# TLC5955.net
KiCad netlist of a schematic drawn in EAGLE
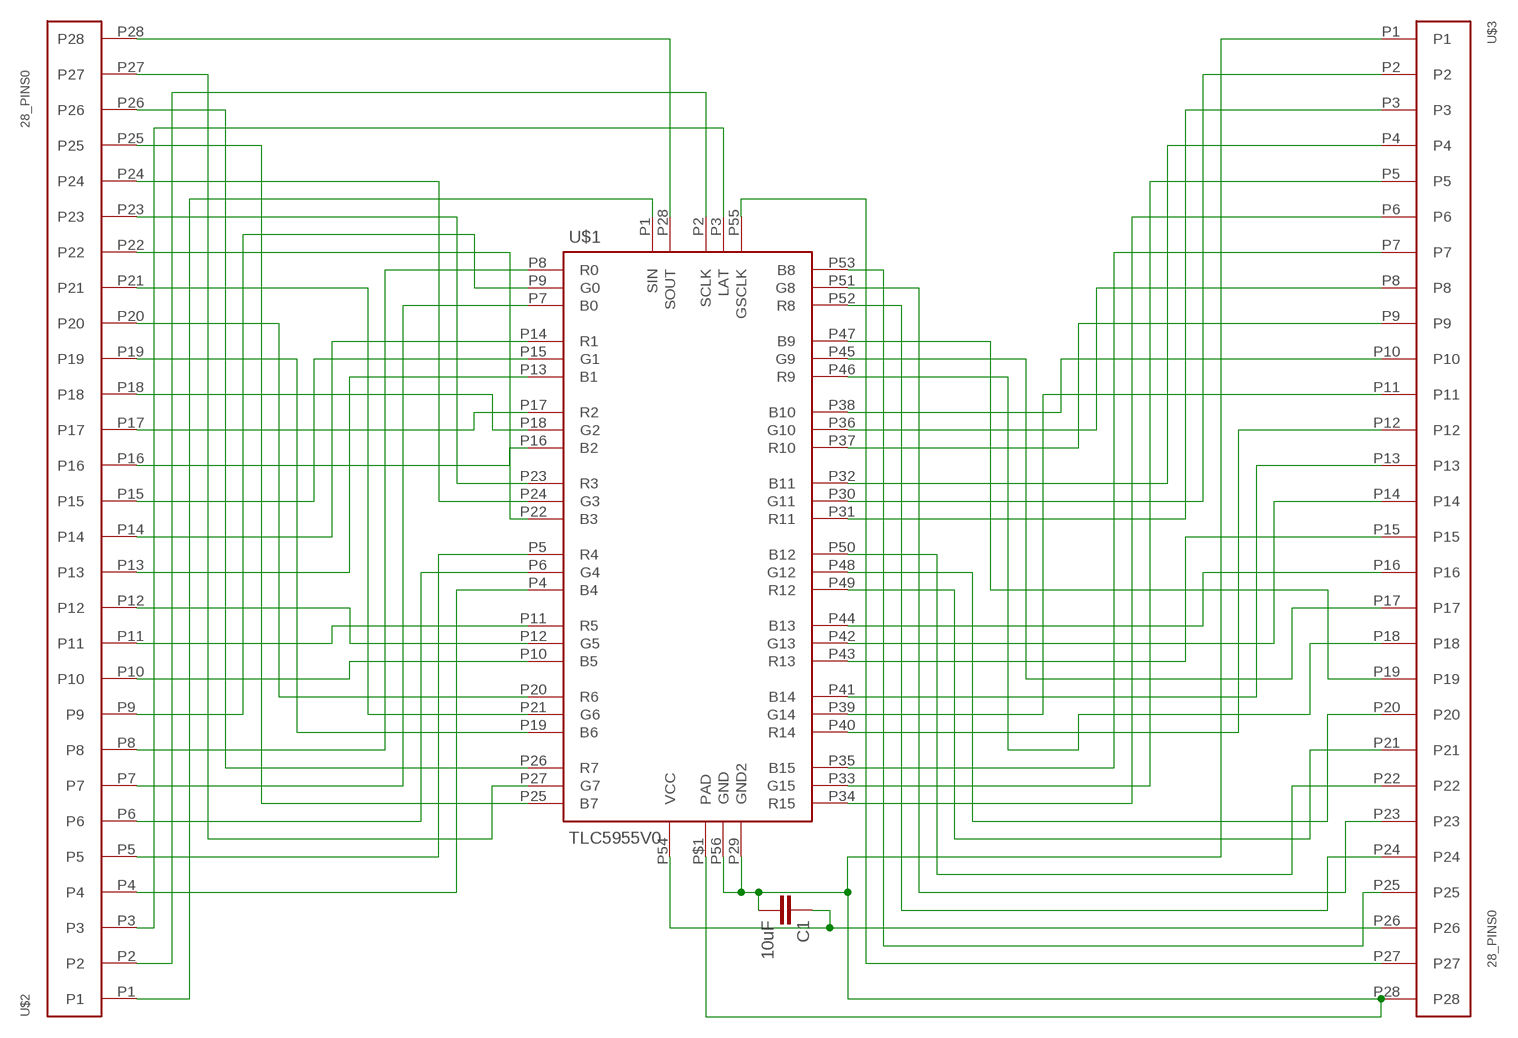
[diagram p0: schematic, sheet 1]

(export (version "E")
  (design (tool "Eeschema 10.0.6"))
  (components
    (comp (ref "C1")
      (value "10uF")
      (footprint "eagle-import:0603-CAP")
      (libsource (lib "eagle-import") (part "10UF-6.3V-20%(0603)"))
    )
    (comp (ref "U$1")
      (value "TLC5955V0")
      (footprint "eagle-import:56-HTSSOP")
      (libsource (lib "eagle-import") (part "TLC5955V0"))
    )
    (comp (ref "U$2")
      (value "28_PINS0")
      (footprint "eagle-import:28PIN_HOLES")
      (libsource (lib "eagle-import") (part "28_PINS0"))
    )
    (comp (ref "U$3")
      (value "28_PINS0")
      (footprint "eagle-import:28PIN_HOLES")
      (libsource (lib "eagle-import") (part "28_PINS0"))
    )
  )
  (nets
    (net (code "1") (name "Net-(U$1-B0)") (class "Default")
      (node (ref "U$1") (pin "P7") (pinfunction "B0_P7") (pintype "bidirectional"))
      (node (ref "U$2") (pin "P7") (pinfunction "P7_P7") (pintype "bidirectional"))
    )
    (net (code "2") (name "Net-(U$1-B1)") (class "Default")
      (node (ref "U$1") (pin "P13") (pinfunction "B1_P13") (pintype "bidirectional"))
      (node (ref "U$2") (pin "P13") (pinfunction "P13_P13") (pintype "bidirectional"))
    )
    (net (code "3") (name "Net-(U$1-B2)") (class "Default")
      (node (ref "U$1") (pin "P16") (pinfunction "B2_P16") (pintype "bidirectional"))
      (node (ref "U$2") (pin "P16") (pinfunction "P16_P16") (pintype "bidirectional"))
    )
    (net (code "4") (name "Net-(U$1-B3)") (class "Default")
      (node (ref "U$1") (pin "P22") (pinfunction "B3_P22") (pintype "bidirectional"))
      (node (ref "U$2") (pin "P22") (pinfunction "P22_P22") (pintype "bidirectional"))
    )
    (net (code "5") (name "Net-(U$1-B4)") (class "Default")
      (node (ref "U$1") (pin "P4") (pinfunction "B4_P4") (pintype "bidirectional"))
      (node (ref "U$2") (pin "P4") (pinfunction "P4_P4") (pintype "bidirectional"))
    )
    (net (code "6") (name "Net-(U$1-B5)") (class "Default")
      (node (ref "U$1") (pin "P10") (pinfunction "B5_P10") (pintype "bidirectional"))
      (node (ref "U$2") (pin "P10") (pinfunction "P10_P10") (pintype "bidirectional"))
    )
    (net (code "7") (name "Net-(U$1-B6)") (class "Default")
      (node (ref "U$1") (pin "P19") (pinfunction "B6_P19") (pintype "bidirectional"))
      (node (ref "U$2") (pin "P19") (pinfunction "P19_P19") (pintype "bidirectional"))
    )
    (net (code "8") (name "Net-(U$1-B7)") (class "Default")
      (node (ref "U$1") (pin "P25") (pinfunction "B7_P25") (pintype "bidirectional"))
      (node (ref "U$2") (pin "P25") (pinfunction "P25_P25") (pintype "bidirectional"))
    )
    (net (code "9") (name "Net-(U$1-B8)") (class "Default")
      (node (ref "U$1") (pin "P53") (pinfunction "B8_P53") (pintype "bidirectional"))
      (node (ref "U$3") (pin "P25") (pinfunction "P25_P25") (pintype "bidirectional"))
    )
    (net (code "10") (name "Net-(U$1-B9)") (class "Default")
      (node (ref "U$1") (pin "P47") (pinfunction "B9_P47") (pintype "bidirectional"))
      (node (ref "U$3") (pin "P19") (pinfunction "P19_P19") (pintype "bidirectional"))
    )
    (net (code "11") (name "Net-(U$1-B10)") (class "Default")
      (node (ref "U$1") (pin "P38") (pinfunction "B10_P38") (pintype "bidirectional"))
      (node (ref "U$3") (pin "P10") (pinfunction "P10_P10") (pintype "bidirectional"))
    )
    (net (code "12") (name "Net-(U$1-B11)") (class "Default")
      (node (ref "U$1") (pin "P32") (pinfunction "B11_P32") (pintype "bidirectional"))
      (node (ref "U$3") (pin "P4") (pinfunction "P4_P4") (pintype "bidirectional"))
    )
    (net (code "13") (name "Net-(U$1-B12)") (class "Default")
      (node (ref "U$1") (pin "P50") (pinfunction "B12_P50") (pintype "bidirectional"))
      (node (ref "U$3") (pin "P22") (pinfunction "P22_P22") (pintype "bidirectional"))
    )
    (net (code "14") (name "Net-(U$1-B13)") (class "Default")
      (node (ref "U$1") (pin "P44") (pinfunction "B13_P44") (pintype "bidirectional"))
      (node (ref "U$3") (pin "P16") (pinfunction "P16_P16") (pintype "bidirectional"))
    )
    (net (code "15") (name "Net-(U$1-B14)") (class "Default")
      (node (ref "U$1") (pin "P41") (pinfunction "B14_P41") (pintype "bidirectional"))
      (node (ref "U$3") (pin "P13") (pinfunction "P13_P13") (pintype "bidirectional"))
    )
    (net (code "16") (name "Net-(U$1-B15)") (class "Default")
      (node (ref "U$1") (pin "P35") (pinfunction "B15_P35") (pintype "bidirectional"))
      (node (ref "U$3") (pin "P7") (pinfunction "P7_P7") (pintype "bidirectional"))
    )
    (net (code "17") (name "Net-(U$1-G0)") (class "Default")
      (node (ref "U$1") (pin "P9") (pinfunction "G0_P9") (pintype "bidirectional"))
      (node (ref "U$2") (pin "P9") (pinfunction "P9_P9") (pintype "bidirectional"))
    )
    (net (code "18") (name "Net-(U$1-G1)") (class "Default")
      (node (ref "U$1") (pin "P15") (pinfunction "G1_P15") (pintype "bidirectional"))
      (node (ref "U$2") (pin "P15") (pinfunction "P15_P15") (pintype "bidirectional"))
    )
    (net (code "19") (name "Net-(U$1-G2)") (class "Default")
      (node (ref "U$1") (pin "P18") (pinfunction "G2_P18") (pintype "bidirectional"))
      (node (ref "U$2") (pin "P18") (pinfunction "P18_P18") (pintype "bidirectional"))
    )
    (net (code "20") (name "Net-(U$1-G3)") (class "Default")
      (node (ref "U$1") (pin "P24") (pinfunction "G3_P24") (pintype "bidirectional"))
      (node (ref "U$2") (pin "P24") (pinfunction "P24_P24") (pintype "bidirectional"))
    )
    (net (code "21") (name "Net-(U$1-G4)") (class "Default")
      (node (ref "U$1") (pin "P6") (pinfunction "G4_P6") (pintype "bidirectional"))
      (node (ref "U$2") (pin "P6") (pinfunction "P6_P6") (pintype "bidirectional"))
    )
    (net (code "22") (name "Net-(U$1-G5)") (class "Default")
      (node (ref "U$1") (pin "P12") (pinfunction "G5_P12") (pintype "bidirectional"))
      (node (ref "U$2") (pin "P12") (pinfunction "P12_P12") (pintype "bidirectional"))
    )
    (net (code "23") (name "Net-(U$1-G6)") (class "Default")
      (node (ref "U$1") (pin "P21") (pinfunction "G6_P21") (pintype "bidirectional"))
      (node (ref "U$2") (pin "P21") (pinfunction "P21_P21") (pintype "bidirectional"))
    )
    (net (code "24") (name "Net-(U$1-G7)") (class "Default")
      (node (ref "U$1") (pin "P27") (pinfunction "G7_P27") (pintype "bidirectional"))
      (node (ref "U$2") (pin "P27") (pinfunction "P27_P27") (pintype "bidirectional"))
    )
    (net (code "25") (name "Net-(U$1-G8)") (class "Default")
      (node (ref "U$1") (pin "P51") (pinfunction "G8_P51") (pintype "bidirectional"))
      (node (ref "U$3") (pin "P23") (pinfunction "P23_P23") (pintype "bidirectional"))
    )
    (net (code "26") (name "Net-(U$1-G9)") (class "Default")
      (node (ref "U$1") (pin "P45") (pinfunction "G9_P45") (pintype "bidirectional"))
      (node (ref "U$3") (pin "P17") (pinfunction "P17_P17") (pintype "bidirectional"))
    )
    (net (code "27") (name "Net-(U$1-G10)") (class "Default")
      (node (ref "U$1") (pin "P36") (pinfunction "G10_P36") (pintype "bidirectional"))
      (node (ref "U$3") (pin "P8") (pinfunction "P8_P8") (pintype "bidirectional"))
    )
    (net (code "28") (name "Net-(U$1-G11)") (class "Default")
      (node (ref "U$1") (pin "P30") (pinfunction "G11_P30") (pintype "bidirectional"))
      (node (ref "U$3") (pin "P2") (pinfunction "P2_P2") (pintype "bidirectional"))
    )
    (net (code "29") (name "Net-(U$1-G12)") (class "Default")
      (node (ref "U$1") (pin "P48") (pinfunction "G12_P48") (pintype "bidirectional"))
      (node (ref "U$3") (pin "P20") (pinfunction "P20_P20") (pintype "bidirectional"))
    )
    (net (code "30") (name "Net-(U$1-G13)") (class "Default")
      (node (ref "U$1") (pin "P42") (pinfunction "G13_P42") (pintype "bidirectional"))
      (node (ref "U$3") (pin "P14") (pinfunction "P14_P14") (pintype "bidirectional"))
    )
    (net (code "31") (name "Net-(U$1-G14)") (class "Default")
      (node (ref "U$1") (pin "P39") (pinfunction "G14_P39") (pintype "bidirectional"))
      (node (ref "U$3") (pin "P11") (pinfunction "P11_P11") (pintype "bidirectional"))
    )
    (net (code "32") (name "Net-(U$1-G15)") (class "Default")
      (node (ref "U$1") (pin "P33") (pinfunction "G15_P33") (pintype "bidirectional"))
      (node (ref "U$3") (pin "P5") (pinfunction "P5_P5") (pintype "bidirectional"))
    )
    (net (code "33") (name "Net-(U$1-GND)") (class "Default")
      (node (ref "C1") (pin "2") (pinfunction "2_2") (pintype "passive"))
      (node (ref "U$1") (pin "P$1") (pinfunction "PAD_P$1") (pintype "bidirectional"))
      (node (ref "U$1") (pin "P29") (pinfunction "GND2_P29") (pintype "bidirectional"))
      (node (ref "U$1") (pin "P56") (pinfunction "GND_P56") (pintype "bidirectional"))
      (node (ref "U$3") (pin "P1") (pinfunction "P1_P1") (pintype "bidirectional"))
      (node (ref "U$3") (pin "P28") (pinfunction "P28_P28") (pintype "bidirectional"))
    )
    (net (code "34") (name "Net-(U$1-GSCLK)") (class "Default")
      (node (ref "U$1") (pin "P55") (pinfunction "GSCLK_P55") (pintype "bidirectional"))
      (node (ref "U$3") (pin "P27") (pinfunction "P27_P27") (pintype "bidirectional"))
    )
    (net (code "35") (name "Net-(U$1-LAT)") (class "Default")
      (node (ref "U$1") (pin "P3") (pinfunction "LAT_P3") (pintype "bidirectional"))
      (node (ref "U$2") (pin "P3") (pinfunction "P3_P3") (pintype "bidirectional"))
    )
    (net (code "36") (name "Net-(U$1-R0)") (class "Default")
      (node (ref "U$1") (pin "P8") (pinfunction "R0_P8") (pintype "bidirectional"))
      (node (ref "U$2") (pin "P8") (pinfunction "P8_P8") (pintype "bidirectional"))
    )
    (net (code "37") (name "Net-(U$1-R1)") (class "Default")
      (node (ref "U$1") (pin "P14") (pinfunction "R1_P14") (pintype "bidirectional"))
      (node (ref "U$2") (pin "P14") (pinfunction "P14_P14") (pintype "bidirectional"))
    )
    (net (code "38") (name "Net-(U$1-R2)") (class "Default")
      (node (ref "U$1") (pin "P17") (pinfunction "R2_P17") (pintype "bidirectional"))
      (node (ref "U$2") (pin "P17") (pinfunction "P17_P17") (pintype "bidirectional"))
    )
    (net (code "39") (name "Net-(U$1-R3)") (class "Default")
      (node (ref "U$1") (pin "P23") (pinfunction "R3_P23") (pintype "bidirectional"))
      (node (ref "U$2") (pin "P23") (pinfunction "P23_P23") (pintype "bidirectional"))
    )
    (net (code "40") (name "Net-(U$1-R4)") (class "Default")
      (node (ref "U$1") (pin "P5") (pinfunction "R4_P5") (pintype "bidirectional"))
      (node (ref "U$2") (pin "P5") (pinfunction "P5_P5") (pintype "bidirectional"))
    )
    (net (code "41") (name "Net-(U$1-R5)") (class "Default")
      (node (ref "U$1") (pin "P11") (pinfunction "R5_P11") (pintype "bidirectional"))
      (node (ref "U$2") (pin "P11") (pinfunction "P11_P11") (pintype "bidirectional"))
    )
    (net (code "42") (name "Net-(U$1-R6)") (class "Default")
      (node (ref "U$1") (pin "P20") (pinfunction "R6_P20") (pintype "bidirectional"))
      (node (ref "U$2") (pin "P20") (pinfunction "P20_P20") (pintype "bidirectional"))
    )
    (net (code "43") (name "Net-(U$1-R7)") (class "Default")
      (node (ref "U$1") (pin "P26") (pinfunction "R7_P26") (pintype "bidirectional"))
      (node (ref "U$2") (pin "P26") (pinfunction "P26_P26") (pintype "bidirectional"))
    )
    (net (code "44") (name "Net-(U$1-R8)") (class "Default")
      (node (ref "U$1") (pin "P52") (pinfunction "R8_P52") (pintype "bidirectional"))
      (node (ref "U$3") (pin "P24") (pinfunction "P24_P24") (pintype "bidirectional"))
    )
    (net (code "45") (name "Net-(U$1-R9)") (class "Default")
      (node (ref "U$1") (pin "P46") (pinfunction "R9_P46") (pintype "bidirectional"))
      (node (ref "U$3") (pin "P18") (pinfunction "P18_P18") (pintype "bidirectional"))
    )
    (net (code "46") (name "Net-(U$1-R10)") (class "Default")
      (node (ref "U$1") (pin "P37") (pinfunction "R10_P37") (pintype "bidirectional"))
      (node (ref "U$3") (pin "P9") (pinfunction "P9_P9") (pintype "bidirectional"))
    )
    (net (code "47") (name "Net-(U$1-R11)") (class "Default")
      (node (ref "U$1") (pin "P31") (pinfunction "R11_P31") (pintype "bidirectional"))
      (node (ref "U$3") (pin "P3") (pinfunction "P3_P3") (pintype "bidirectional"))
    )
    (net (code "48") (name "Net-(U$1-R12)") (class "Default")
      (node (ref "U$1") (pin "P49") (pinfunction "R12_P49") (pintype "bidirectional"))
      (node (ref "U$3") (pin "P21") (pinfunction "P21_P21") (pintype "bidirectional"))
    )
    (net (code "49") (name "Net-(U$1-R13)") (class "Default")
      (node (ref "U$1") (pin "P43") (pinfunction "R13_P43") (pintype "bidirectional"))
      (node (ref "U$3") (pin "P15") (pinfunction "P15_P15") (pintype "bidirectional"))
    )
    (net (code "50") (name "Net-(U$1-R14)") (class "Default")
      (node (ref "U$1") (pin "P40") (pinfunction "R14_P40") (pintype "bidirectional"))
      (node (ref "U$3") (pin "P12") (pinfunction "P12_P12") (pintype "bidirectional"))
    )
    (net (code "51") (name "Net-(U$1-R15)") (class "Default")
      (node (ref "U$1") (pin "P34") (pinfunction "R15_P34") (pintype "bidirectional"))
      (node (ref "U$3") (pin "P6") (pinfunction "P6_P6") (pintype "bidirectional"))
    )
    (net (code "52") (name "Net-(U$1-SCLK)") (class "Default")
      (node (ref "U$1") (pin "P2") (pinfunction "SCLK_P2") (pintype "bidirectional"))
      (node (ref "U$2") (pin "P2") (pinfunction "P2_P2") (pintype "bidirectional"))
    )
    (net (code "53") (name "Net-(U$1-SIN)") (class "Default")
      (node (ref "U$1") (pin "P1") (pinfunction "SIN_P1") (pintype "bidirectional"))
      (node (ref "U$2") (pin "P1") (pinfunction "P1_P1") (pintype "bidirectional"))
    )
    (net (code "54") (name "Net-(U$1-SOUT)") (class "Default")
      (node (ref "U$1") (pin "P28") (pinfunction "SOUT_P28") (pintype "bidirectional"))
      (node (ref "U$2") (pin "P28") (pinfunction "P28_P28") (pintype "bidirectional"))
    )
    (net (code "55") (name "Net-(U$1-VCC)") (class "Default")
      (node (ref "C1") (pin "1") (pinfunction "1_1") (pintype "passive"))
      (node (ref "U$1") (pin "P54") (pinfunction "VCC_P54") (pintype "bidirectional"))
      (node (ref "U$3") (pin "P26") (pinfunction "P26_P26") (pintype "bidirectional"))
    )
  )
)
